# PIC_HP_LED_2023_01_22_A.net
KiCad netlist of a schematic drawn in EAGLE
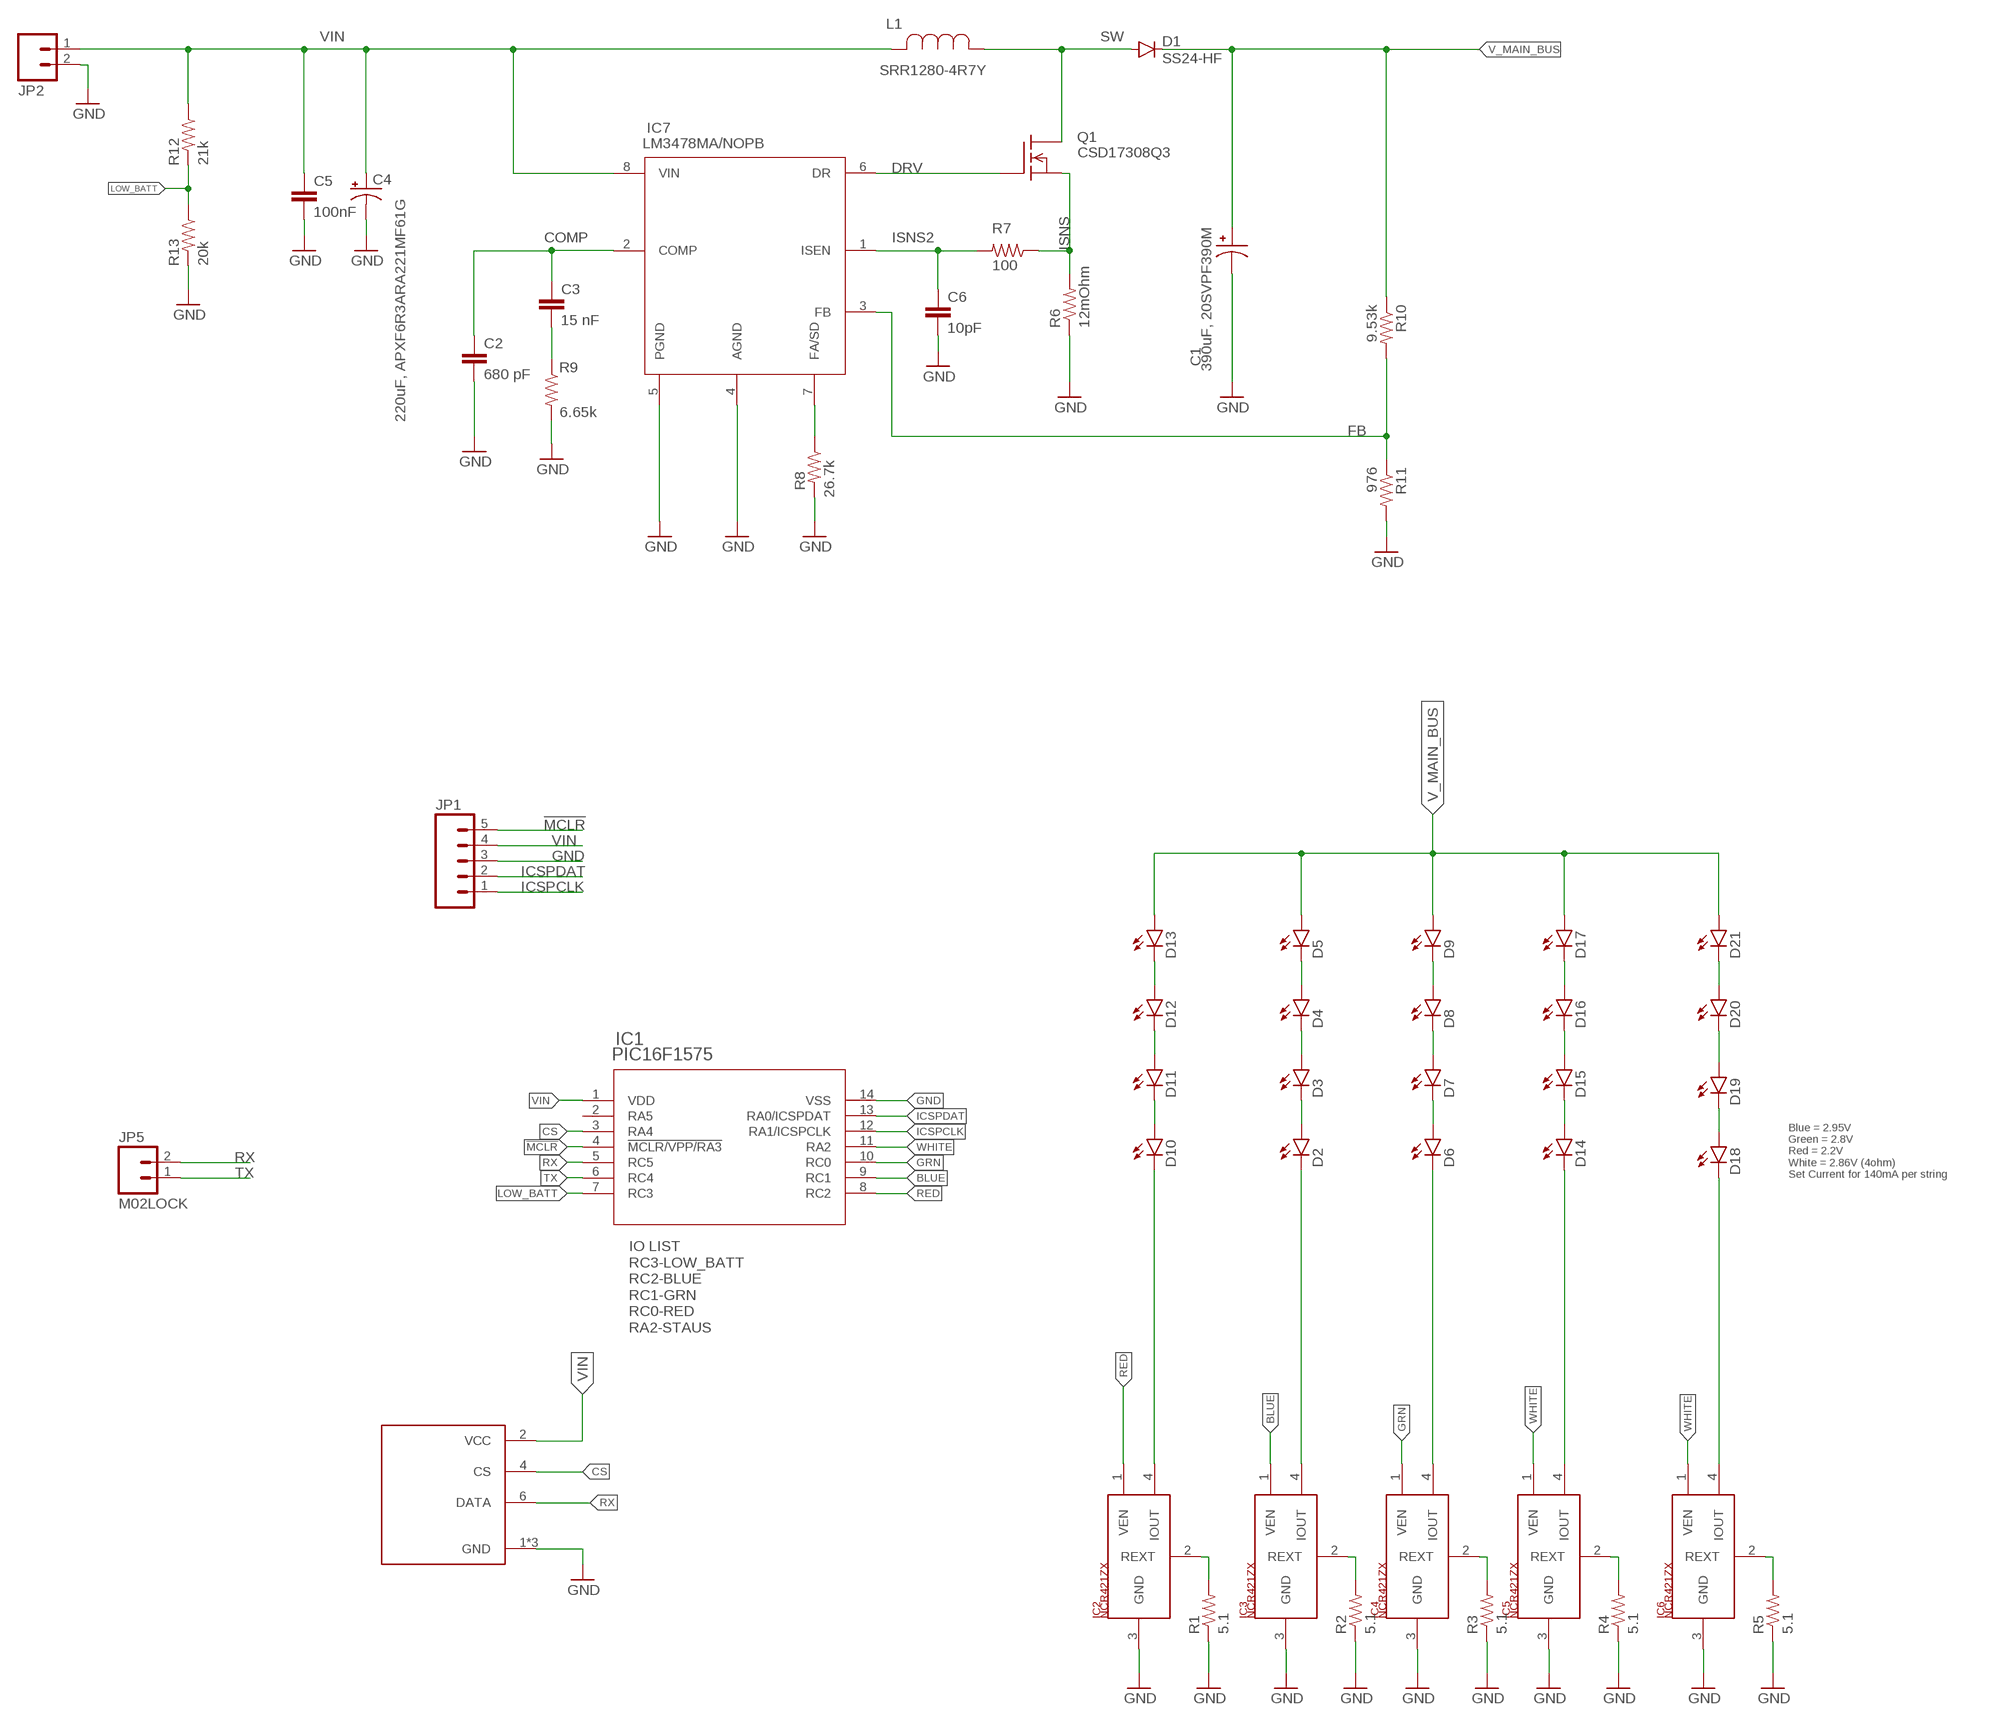
[diagram p0: schematic, sheet 1]

(export (version "E")
  (design (tool "Eeschema 10.0.6"))
  (components
    (comp (ref "C1")
      (value "390uF, 20SVPF390M")
      (footprint "eagle-import:CAP_20SVPF390M")
      (fields (field (name "MF") "Panasonic") (field (name "MP") "20SVPF390M"))
      (libsource (lib "eagle-import") (part "20SVPF390M"))
    )
    (comp (ref "C2")
      (value "680 pF")
      (footprint "eagle-import:0805")
      (libsource (lib "eagle-import") (part "CAP0805"))
    )
    (comp (ref "C3")
      (value "15 nF")
      (footprint "eagle-import:0805")
      (libsource (lib "eagle-import") (part "CAP0805"))
    )
    (comp (ref "C4")
      (value "220uF, APXF6R3ARA221MF61G")
      (footprint "eagle-import:UD-5X5,8_NICHICON")
      (libsource (lib "eagle-import") (part "CPOL-USUD-5X5,8"))
    )
    (comp (ref "C5")
      (value "100nF")
      (footprint "eagle-import:0805")
      (libsource (lib "eagle-import") (part "CAP0805"))
    )
    (comp (ref "C6")
      (value "10pF")
      (footprint "eagle-import:0805")
      (libsource (lib "eagle-import") (part "CAP0805"))
    )
    (comp (ref "D1")
      (value "SS24-HF")
      (footprint "eagle-import:SMA-DIODE_ALT")
      (libsource (lib "eagle-import") (part "DIODESMA-ALT"))
    )
    (comp (ref "D2")
      (value "JE2835_B_G")
      (footprint "eagle-import:JE2835_BLUE")
      (libsource (lib "eagle-import") (part "JE2835_B_G"))
    )
    (comp (ref "D3")
      (value "JE2835_B_G")
      (footprint "eagle-import:JE2835_BLUE")
      (libsource (lib "eagle-import") (part "JE2835_B_G"))
    )
    (comp (ref "D4")
      (value "JE2835_B_G")
      (footprint "eagle-import:JE2835_BLUE")
      (libsource (lib "eagle-import") (part "JE2835_B_G"))
    )
    (comp (ref "D5")
      (value "JE2835_B_G")
      (footprint "eagle-import:JE2835_BLUE")
      (libsource (lib "eagle-import") (part "JE2835_B_G"))
    )
    (comp (ref "D6")
      (value "JE2835_B_G")
      (footprint "eagle-import:JE2835_BLUE")
      (libsource (lib "eagle-import") (part "JE2835_B_G"))
    )
    (comp (ref "D7")
      (value "JE2835_B_G")
      (footprint "eagle-import:JE2835_BLUE")
      (libsource (lib "eagle-import") (part "JE2835_B_G"))
    )
    (comp (ref "D8")
      (value "JE2835_B_G")
      (footprint "eagle-import:JE2835_BLUE")
      (libsource (lib "eagle-import") (part "JE2835_B_G"))
    )
    (comp (ref "D9")
      (value "JE2835_B_G")
      (footprint "eagle-import:JE2835_BLUE")
      (libsource (lib "eagle-import") (part "JE2835_B_G"))
    )
    (comp (ref "D10")
      (value "JE2835_B_G")
      (footprint "eagle-import:JE2835_BLUE")
      (libsource (lib "eagle-import") (part "JE2835_B_G"))
    )
    (comp (ref "D11")
      (value "JE2835_B_G")
      (footprint "eagle-import:JE2835_BLUE")
      (libsource (lib "eagle-import") (part "JE2835_B_G"))
    )
    (comp (ref "D12")
      (value "JE2835_B_G")
      (footprint "eagle-import:JE2835_BLUE")
      (libsource (lib "eagle-import") (part "JE2835_B_G"))
    )
    (comp (ref "D13")
      (value "JE2835_B_G")
      (footprint "eagle-import:JE2835_BLUE")
      (libsource (lib "eagle-import") (part "JE2835_B_G"))
    )
    (comp (ref "D14")
      (value "JE2835_B_G")
      (footprint "eagle-import:JE2835_BLUE")
      (libsource (lib "eagle-import") (part "JE2835_B_G"))
    )
    (comp (ref "D15")
      (value "JE2835_B_G")
      (footprint "eagle-import:JE2835_BLUE")
      (libsource (lib "eagle-import") (part "JE2835_B_G"))
    )
    (comp (ref "D16")
      (value "JE2835_B_G")
      (footprint "eagle-import:JE2835_BLUE")
      (libsource (lib "eagle-import") (part "JE2835_B_G"))
    )
    (comp (ref "D17")
      (value "JE2835_B_G")
      (footprint "eagle-import:JE2835_BLUE")
      (libsource (lib "eagle-import") (part "JE2835_B_G"))
    )
    (comp (ref "D18")
      (value "JE2835_B_G")
      (footprint "eagle-import:JE2835_BLUE")
      (libsource (lib "eagle-import") (part "JE2835_B_G"))
    )
    (comp (ref "D19")
      (value "JE2835_B_G")
      (footprint "eagle-import:JE2835_BLUE")
      (libsource (lib "eagle-import") (part "JE2835_B_G"))
    )
    (comp (ref "D20")
      (value "JE2835_B_G")
      (footprint "eagle-import:JE2835_BLUE")
      (libsource (lib "eagle-import") (part "JE2835_B_G"))
    )
    (comp (ref "D21")
      (value "JE2835_B_G")
      (footprint "eagle-import:JE2835_BLUE")
      (libsource (lib "eagle-import") (part "JE2835_B_G"))
    )
    (comp (ref "IC1")
      (value "PIC16F1575")
      (footprint "eagle-import:SOIC14_SL")
      (fields (field (name "MANUFACTURER_PART_NUMBER") "PIC16F1503-I/SL"))
      (libsource (lib "eagle-import") (part "PIC16F1503-I/SL"))
    )
    (comp (ref "IC2")
      (value "NCR421ZX")
      (footprint "eagle-import:SOT223")
      (libsource (lib "eagle-import") (part "NCR421ZX"))
    )
    (comp (ref "IC3")
      (value "NCR421ZX")
      (footprint "eagle-import:SOT223")
      (libsource (lib "eagle-import") (part "NCR421ZX"))
    )
    (comp (ref "IC4")
      (value "NCR421ZX")
      (footprint "eagle-import:SOT223")
      (libsource (lib "eagle-import") (part "NCR421ZX"))
    )
    (comp (ref "IC5")
      (value "NCR421ZX")
      (footprint "eagle-import:SOT223")
      (libsource (lib "eagle-import") (part "NCR421ZX"))
    )
    (comp (ref "IC6")
      (value "NCR421ZX")
      (footprint "eagle-import:SOT223")
      (libsource (lib "eagle-import") (part "NCR421ZX"))
    )
    (comp (ref "IC7")
      (value "LM3478MA/NOPB")
      (footprint "eagle-import:M08A")
      (fields (field (name "COPYRIGHT") "Copyright (C) 2022 Ultra Librarian. All rights reserved."))
      (libsource (lib "eagle-import") (part "LM3478MA/NOPB"))
    )
    (comp (ref "JP1")
      (value "M05LOCK")
      (footprint "eagle-import:1X05_LOCK")
      (libsource (lib "eagle-import") (part "M05LOCK"))
    )
    (comp (ref "JP2")
      (value "M02LOCK_LONGPADS")
      (footprint "eagle-import:1X02_LOCK_LONGPADS")
      (libsource (lib "eagle-import") (part "M02LOCK_LONGPADS"))
    )
    (comp (ref "JP5")
      (value "M02LOCK")
      (footprint "eagle-import:1X02_LOCK")
      (libsource (lib "eagle-import") (part "M02LOCK"))
    )
    (comp (ref "L1")
      (value "SRR1280-4R7Y")
      (footprint "eagle-import:IND_BOURNS_SRR1260")
      (fields
        (field (name "MANUFACTURER_PART_NUMBER") "SRR1260-100M")
        (field (name "COPYRIGHT") "Copyright (C) 2021 Ultra Librarian. All rights reserved.")
      )
      (libsource (lib "eagle-import") (part "SRR1260-100M"))
    )
    (comp (ref "Q1")
      (value "CSD17308Q3")
      (footprint "eagle-import:TRANS_CSD17308Q3")
      (fields (field (name "MF") "Texas Instruments"))
      (libsource (lib "eagle-import") (part "CSD17308Q3"))
    )
    (comp (ref "R1")
      (value "5.1")
      (footprint "eagle-import:1206")
      (libsource (lib "eagle-import") (part "RESISTOR1206"))
    )
    (comp (ref "R2")
      (value "5.1")
      (footprint "eagle-import:1206")
      (libsource (lib "eagle-import") (part "RESISTOR1206"))
    )
    (comp (ref "R3")
      (value "5.1")
      (footprint "eagle-import:1206")
      (libsource (lib "eagle-import") (part "RESISTOR1206"))
    )
    (comp (ref "R4")
      (value "5.1")
      (footprint "eagle-import:1206")
      (libsource (lib "eagle-import") (part "RESISTOR1206"))
    )
    (comp (ref "R5")
      (value "5.1")
      (footprint "eagle-import:1206")
      (libsource (lib "eagle-import") (part "RESISTOR1206"))
    )
    (comp (ref "R6")
      (value "12mOhm")
      (footprint "eagle-import:0805")
      (libsource (lib "eagle-import") (part "RESISTOR0805-RES"))
    )
    (comp (ref "R7")
      (value "100")
      (footprint "eagle-import:0805")
      (libsource (lib "eagle-import") (part "RESISTOR0805-RES"))
    )
    (comp (ref "R8")
      (value "26.7k")
      (footprint "eagle-import:0805")
      (libsource (lib "eagle-import") (part "RESISTOR0805-RES"))
    )
    (comp (ref "R9")
      (value "6.65k")
      (footprint "eagle-import:0805")
      (libsource (lib "eagle-import") (part "RESISTOR0805-RES"))
    )
    (comp (ref "R10")
      (value "9.53k")
      (footprint "eagle-import:0805")
      (libsource (lib "eagle-import") (part "RESISTOR0805-RES"))
    )
    (comp (ref "R11")
      (value "976")
      (footprint "eagle-import:0805")
      (libsource (lib "eagle-import") (part "RESISTOR0805-RES"))
    )
    (comp (ref "R12")
      (value "21k")
      (footprint "eagle-import:0805")
      (libsource (lib "eagle-import") (part "RESISTOR0805-RES"))
    )
    (comp (ref "R13")
      (value "20k")
      (footprint "eagle-import:0805")
      (libsource (lib "eagle-import") (part "RESISTOR0805-RES"))
    )
    (comp (ref "U$1")
      (value "C2847244/YUANR4A")
      (footprint "eagle-import:C2847244_R4A")
      (libsource (lib "eagle-import") (part "C2847244/YUANR4A"))
    )
  )
  (nets
    (net (code "1") (name "/COMP") (class "Default")
      (node (ref "C2") (pin "1") (pinfunction "1_1") (pintype "passive"))
      (node (ref "C3") (pin "1") (pinfunction "1_1") (pintype "passive"))
      (node (ref "IC7") (pin "2") (pinfunction "COMP_2") (pintype "passive"))
    )
    (net (code "2") (name "/DRV") (class "Default")
      (node (ref "IC7") (pin "6") (pinfunction "DR_6") (pintype "passive"))
      (node (ref "Q1") (pin "G") (pinfunction "G_G") (pintype "passive"))
    )
    (net (code "3") (name "/FB") (class "Default")
      (node (ref "IC7") (pin "3") (pinfunction "FB_3") (pintype "output"))
      (node (ref "R10") (pin "2") (pinfunction "2_2") (pintype "passive"))
      (node (ref "R11") (pin "1") (pinfunction "1_1") (pintype "passive"))
    )
    (net (code "4") (name "/ISNS") (class "Default")
      (node (ref "Q1") (pin "S1") (pinfunction "S_S1") (pintype "passive"))
      (node (ref "Q1") (pin "S2") (pinfunction "S_S2") (pintype "passive"))
      (node (ref "Q1") (pin "S3") (pinfunction "S_S3") (pintype "passive"))
      (node (ref "R6") (pin "2") (pinfunction "2_2") (pintype "passive"))
      (node (ref "R7") (pin "1") (pinfunction "1_1") (pintype "passive"))
    )
    (net (code "5") (name "/ISNS2") (class "Default")
      (node (ref "C6") (pin "1") (pinfunction "1_1") (pintype "passive"))
      (node (ref "IC7") (pin "1") (pinfunction "ISEN_1") (pintype "input"))
      (node (ref "R7") (pin "2") (pinfunction "2_2") (pintype "passive"))
    )
    (net (code "6") (name "/SW") (class "Default")
      (node (ref "D1") (pin "A") (pinfunction "A_A") (pintype "passive"))
      (node (ref "L1") (pin "1") (pinfunction "1_1") (pintype "passive"))
      (node (ref "Q1") (pin "5-8") (pinfunction "D_5-8") (pintype "passive"))
    )
    (net (code "7") (name "/~{MCLR}") (class "Default")
      (node (ref "IC1") (pin "4") (pinfunction "~{MCLR/VPP/RA3}_4") (pintype "bidirectional"))
      (node (ref "JP1") (pin "5") (pinfunction "5_5") (pintype "passive"))
    )
    (net (code "8") (name "BLUE") (class "Default")
      (node (ref "IC1") (pin "9") (pinfunction "RC1_9") (pintype "bidirectional"))
      (node (ref "IC3") (pin "1") (pinfunction "VEN_1") (pintype "bidirectional"))
    )
    (net (code "9") (name "CS") (class "Default")
      (node (ref "IC1") (pin "3") (pinfunction "RA4_3") (pintype "bidirectional"))
      (node (ref "U$1") (pin "4") (pinfunction "CS_4") (pintype "bidirectional"))
    )
    (net (code "10") (name "GND") (class "Default")
      (node (ref "C1") (pin "2") (pinfunction "2_2") (pintype "passive"))
      (node (ref "C2") (pin "2") (pinfunction "2_2") (pintype "passive"))
      (node (ref "C4") (pin "-") (pinfunction "-_-") (pintype "passive"))
      (node (ref "C5") (pin "2") (pinfunction "2_2") (pintype "passive"))
      (node (ref "C6") (pin "2") (pinfunction "2_2") (pintype "passive"))
      (node (ref "IC1") (pin "14") (pinfunction "VSS_14") (pintype "power_in"))
      (node (ref "IC2") (pin "3") (pinfunction "GND_3") (pintype "bidirectional"))
      (node (ref "IC3") (pin "3") (pinfunction "GND_3") (pintype "bidirectional"))
      (node (ref "IC4") (pin "3") (pinfunction "GND_3") (pintype "bidirectional"))
      (node (ref "IC5") (pin "3") (pinfunction "GND_3") (pintype "bidirectional"))
      (node (ref "IC6") (pin "3") (pinfunction "GND_3") (pintype "bidirectional"))
      (node (ref "IC7") (pin "4") (pinfunction "AGND_4") (pintype "power_in"))
      (node (ref "IC7") (pin "5") (pinfunction "PGND_5") (pintype "power_in"))
      (node (ref "JP1") (pin "3") (pinfunction "3_3") (pintype "passive"))
      (node (ref "JP2") (pin "2") (pinfunction "2_2") (pintype "passive"))
      (node (ref "R1") (pin "1") (pinfunction "1_1") (pintype "passive"))
      (node (ref "R11") (pin "2") (pinfunction "2_2") (pintype "passive"))
      (node (ref "R13") (pin "2") (pinfunction "2_2") (pintype "passive"))
      (node (ref "R2") (pin "1") (pinfunction "1_1") (pintype "passive"))
      (node (ref "R3") (pin "1") (pinfunction "1_1") (pintype "passive"))
      (node (ref "R4") (pin "1") (pinfunction "1_1") (pintype "passive"))
      (node (ref "R5") (pin "1") (pinfunction "1_1") (pintype "passive"))
      (node (ref "R6") (pin "1") (pinfunction "1_1") (pintype "passive"))
      (node (ref "R8") (pin "2") (pinfunction "2_2") (pintype "passive"))
      (node (ref "R9") (pin "2") (pinfunction "2_2") (pintype "passive"))
      (node (ref "U$1") (pin "1") (pinfunction "GND_1") (pintype "bidirectional"))
      (node (ref "U$1") (pin "3") (pinfunction "GND_3") (pintype "bidirectional"))
      (node (ref "U$1") (pin "5") (pinfunction "GND_5") (pintype "bidirectional"))
    )
    (net (code "11") (name "GRN") (class "Default")
      (node (ref "IC1") (pin "10") (pinfunction "RC0_10") (pintype "bidirectional"))
      (node (ref "IC4") (pin "1") (pinfunction "VEN_1") (pintype "bidirectional"))
    )
    (net (code "12") (name "ICSPCLK") (class "Default")
      (node (ref "IC1") (pin "12") (pinfunction "RA1/ICSPCLK_12") (pintype "bidirectional"))
      (node (ref "JP1") (pin "1") (pinfunction "1_1") (pintype "passive"))
    )
    (net (code "13") (name "ICSPDAT") (class "Default")
      (node (ref "IC1") (pin "13") (pinfunction "RA0/ICSPDAT_13") (pintype "bidirectional"))
      (node (ref "JP1") (pin "2") (pinfunction "2_2") (pintype "passive"))
    )
    (net (code "14") (name "LOW_BATT") (class "Default")
      (node (ref "IC1") (pin "7") (pinfunction "RC3_7") (pintype "bidirectional"))
      (node (ref "R12") (pin "2") (pinfunction "2_2") (pintype "passive"))
      (node (ref "R13") (pin "1") (pinfunction "1_1") (pintype "passive"))
    )
    (net (code "15") (name "Net-(C3-Pad2)") (class "Default")
      (node (ref "C3") (pin "2") (pinfunction "2_2") (pintype "passive"))
      (node (ref "R9") (pin "1") (pinfunction "1_1") (pintype "passive"))
    )
    (net (code "16") (name "Net-(D2-PadA)") (class "Default")
      (node (ref "D2") (pin "A") (pinfunction "A_A") (pintype "passive"))
      (node (ref "D3") (pin "C") (pinfunction "C_C") (pintype "passive"))
    )
    (net (code "17") (name "Net-(D3-PadA)") (class "Default")
      (node (ref "D3") (pin "A") (pinfunction "A_A") (pintype "passive"))
      (node (ref "D4") (pin "C") (pinfunction "C_C") (pintype "passive"))
    )
    (net (code "18") (name "Net-(D4-PadA)") (class "Default")
      (node (ref "D4") (pin "A") (pinfunction "A_A") (pintype "passive"))
      (node (ref "D5") (pin "C") (pinfunction "C_C") (pintype "passive"))
    )
    (net (code "19") (name "Net-(D6-PadA)") (class "Default")
      (node (ref "D6") (pin "A") (pinfunction "A_A") (pintype "passive"))
      (node (ref "D7") (pin "C") (pinfunction "C_C") (pintype "passive"))
    )
    (net (code "20") (name "Net-(D7-PadA)") (class "Default")
      (node (ref "D7") (pin "A") (pinfunction "A_A") (pintype "passive"))
      (node (ref "D8") (pin "C") (pinfunction "C_C") (pintype "passive"))
    )
    (net (code "21") (name "Net-(D8-PadA)") (class "Default")
      (node (ref "D8") (pin "A") (pinfunction "A_A") (pintype "passive"))
      (node (ref "D9") (pin "C") (pinfunction "C_C") (pintype "passive"))
    )
    (net (code "22") (name "Net-(D10-PadA)") (class "Default")
      (node (ref "D10") (pin "A") (pinfunction "A_A") (pintype "passive"))
      (node (ref "D11") (pin "C") (pinfunction "C_C") (pintype "passive"))
    )
    (net (code "23") (name "Net-(D11-PadA)") (class "Default")
      (node (ref "D11") (pin "A") (pinfunction "A_A") (pintype "passive"))
      (node (ref "D12") (pin "C") (pinfunction "C_C") (pintype "passive"))
    )
    (net (code "24") (name "Net-(D12-PadA)") (class "Default")
      (node (ref "D12") (pin "A") (pinfunction "A_A") (pintype "passive"))
      (node (ref "D13") (pin "C") (pinfunction "C_C") (pintype "passive"))
    )
    (net (code "25") (name "Net-(D14-PadA)") (class "Default")
      (node (ref "D14") (pin "A") (pinfunction "A_A") (pintype "passive"))
      (node (ref "D15") (pin "C") (pinfunction "C_C") (pintype "passive"))
    )
    (net (code "26") (name "Net-(D15-PadA)") (class "Default")
      (node (ref "D15") (pin "A") (pinfunction "A_A") (pintype "passive"))
      (node (ref "D16") (pin "C") (pinfunction "C_C") (pintype "passive"))
    )
    (net (code "27") (name "Net-(D16-PadA)") (class "Default")
      (node (ref "D16") (pin "A") (pinfunction "A_A") (pintype "passive"))
      (node (ref "D17") (pin "C") (pinfunction "C_C") (pintype "passive"))
    )
    (net (code "28") (name "Net-(D18-PadA)") (class "Default")
      (node (ref "D18") (pin "A") (pinfunction "A_A") (pintype "passive"))
      (node (ref "D19") (pin "C") (pinfunction "C_C") (pintype "passive"))
    )
    (net (code "29") (name "Net-(D19-PadA)") (class "Default")
      (node (ref "D19") (pin "A") (pinfunction "A_A") (pintype "passive"))
      (node (ref "D20") (pin "C") (pinfunction "C_C") (pintype "passive"))
    )
    (net (code "30") (name "Net-(D20-PadA)") (class "Default")
      (node (ref "D20") (pin "A") (pinfunction "A_A") (pintype "passive"))
      (node (ref "D21") (pin "C") (pinfunction "C_C") (pintype "passive"))
    )
    (net (code "31") (name "Net-(IC2-IOUT)") (class "Default")
      (node (ref "D10") (pin "C") (pinfunction "C_C") (pintype "passive"))
      (node (ref "IC2") (pin "4") (pinfunction "IOUT_4") (pintype "bidirectional"))
    )
    (net (code "32") (name "Net-(IC2-REXT)") (class "Default")
      (node (ref "IC2") (pin "2") (pinfunction "REXT_2") (pintype "bidirectional"))
      (node (ref "R1") (pin "2") (pinfunction "2_2") (pintype "passive"))
    )
    (net (code "33") (name "Net-(IC3-IOUT)") (class "Default")
      (node (ref "D2") (pin "C") (pinfunction "C_C") (pintype "passive"))
      (node (ref "IC3") (pin "4") (pinfunction "IOUT_4") (pintype "bidirectional"))
    )
    (net (code "34") (name "Net-(IC3-REXT)") (class "Default")
      (node (ref "IC3") (pin "2") (pinfunction "REXT_2") (pintype "bidirectional"))
      (node (ref "R2") (pin "2") (pinfunction "2_2") (pintype "passive"))
    )
    (net (code "35") (name "Net-(IC4-IOUT)") (class "Default")
      (node (ref "D6") (pin "C") (pinfunction "C_C") (pintype "passive"))
      (node (ref "IC4") (pin "4") (pinfunction "IOUT_4") (pintype "bidirectional"))
    )
    (net (code "36") (name "Net-(IC4-REXT)") (class "Default")
      (node (ref "IC4") (pin "2") (pinfunction "REXT_2") (pintype "bidirectional"))
      (node (ref "R3") (pin "2") (pinfunction "2_2") (pintype "passive"))
    )
    (net (code "37") (name "Net-(IC5-IOUT)") (class "Default")
      (node (ref "D14") (pin "C") (pinfunction "C_C") (pintype "passive"))
      (node (ref "IC5") (pin "4") (pinfunction "IOUT_4") (pintype "bidirectional"))
    )
    (net (code "38") (name "Net-(IC5-REXT)") (class "Default")
      (node (ref "IC5") (pin "2") (pinfunction "REXT_2") (pintype "bidirectional"))
      (node (ref "R4") (pin "2") (pinfunction "2_2") (pintype "passive"))
    )
    (net (code "39") (name "Net-(IC6-IOUT)") (class "Default")
      (node (ref "D18") (pin "C") (pinfunction "C_C") (pintype "passive"))
      (node (ref "IC6") (pin "4") (pinfunction "IOUT_4") (pintype "bidirectional"))
    )
    (net (code "40") (name "Net-(IC6-REXT)") (class "Default")
      (node (ref "IC6") (pin "2") (pinfunction "REXT_2") (pintype "bidirectional"))
      (node (ref "R5") (pin "2") (pinfunction "2_2") (pintype "passive"))
    )
    (net (code "41") (name "Net-(IC7-FA{slash}SD)") (class "Default")
      (node (ref "IC7") (pin "7") (pinfunction "FA/SD_7") (pintype "bidirectional"))
      (node (ref "R8") (pin "1") (pinfunction "1_1") (pintype "passive"))
    )
    (net (code "42") (name "RED") (class "Default")
      (node (ref "IC1") (pin "8") (pinfunction "RC2_8") (pintype "bidirectional"))
      (node (ref "IC2") (pin "1") (pinfunction "VEN_1") (pintype "bidirectional"))
    )
    (net (code "43") (name "RX") (class "Default")
      (node (ref "IC1") (pin "5") (pinfunction "RC5_5") (pintype "bidirectional"))
      (node (ref "JP5") (pin "2") (pinfunction "2_2") (pintype "passive"))
      (node (ref "U$1") (pin "6") (pinfunction "DATA_6") (pintype "bidirectional"))
    )
    (net (code "44") (name "TX") (class "Default")
      (node (ref "IC1") (pin "6") (pinfunction "RC4_6") (pintype "bidirectional"))
      (node (ref "JP5") (pin "1") (pinfunction "1_1") (pintype "passive"))
    )
    (net (code "45") (name "VIN") (class "Default")
      (node (ref "C4") (pin "+") (pinfunction "+_+") (pintype "passive"))
      (node (ref "C5") (pin "1") (pinfunction "1_1") (pintype "passive"))
      (node (ref "IC1") (pin "1") (pinfunction "VDD_1") (pintype "power_in"))
      (node (ref "IC7") (pin "8") (pinfunction "VIN_8") (pintype "input"))
      (node (ref "JP1") (pin "4") (pinfunction "4_4") (pintype "passive"))
      (node (ref "JP2") (pin "1") (pinfunction "1_1") (pintype "passive"))
      (node (ref "L1") (pin "2") (pinfunction "2_2") (pintype "passive"))
      (node (ref "R12") (pin "1") (pinfunction "1_1") (pintype "passive"))
      (node (ref "U$1") (pin "2") (pinfunction "VCC_2") (pintype "bidirectional"))
    )
    (net (code "46") (name "V_MAIN_BUS") (class "Default")
      (node (ref "C1") (pin "1") (pinfunction "1_1") (pintype "passive"))
      (node (ref "D1") (pin "C") (pinfunction "C_C") (pintype "passive"))
      (node (ref "D13") (pin "A") (pinfunction "A_A") (pintype "passive"))
      (node (ref "D17") (pin "A") (pinfunction "A_A") (pintype "passive"))
      (node (ref "D21") (pin "A") (pinfunction "A_A") (pintype "passive"))
      (node (ref "D5") (pin "A") (pinfunction "A_A") (pintype "passive"))
      (node (ref "D9") (pin "A") (pinfunction "A_A") (pintype "passive"))
      (node (ref "R10") (pin "1") (pinfunction "1_1") (pintype "passive"))
    )
    (net (code "47") (name "WHITE") (class "Default")
      (node (ref "IC1") (pin "11") (pinfunction "RA2_11") (pintype "bidirectional"))
      (node (ref "IC5") (pin "1") (pinfunction "VEN_1") (pintype "bidirectional"))
      (node (ref "IC6") (pin "1") (pinfunction "VEN_1") (pintype "bidirectional"))
    )
    (net (code "48") (name "unconnected-(IC1-RA5-Pad2)") (class "Default")
      (node (ref "IC1") (pin "2") (pinfunction "RA5_2") (pintype "bidirectional"))
    )
  )
)
